# Tachometer-Board.net
KiCad netlist of a schematic drawn in Altium Designer
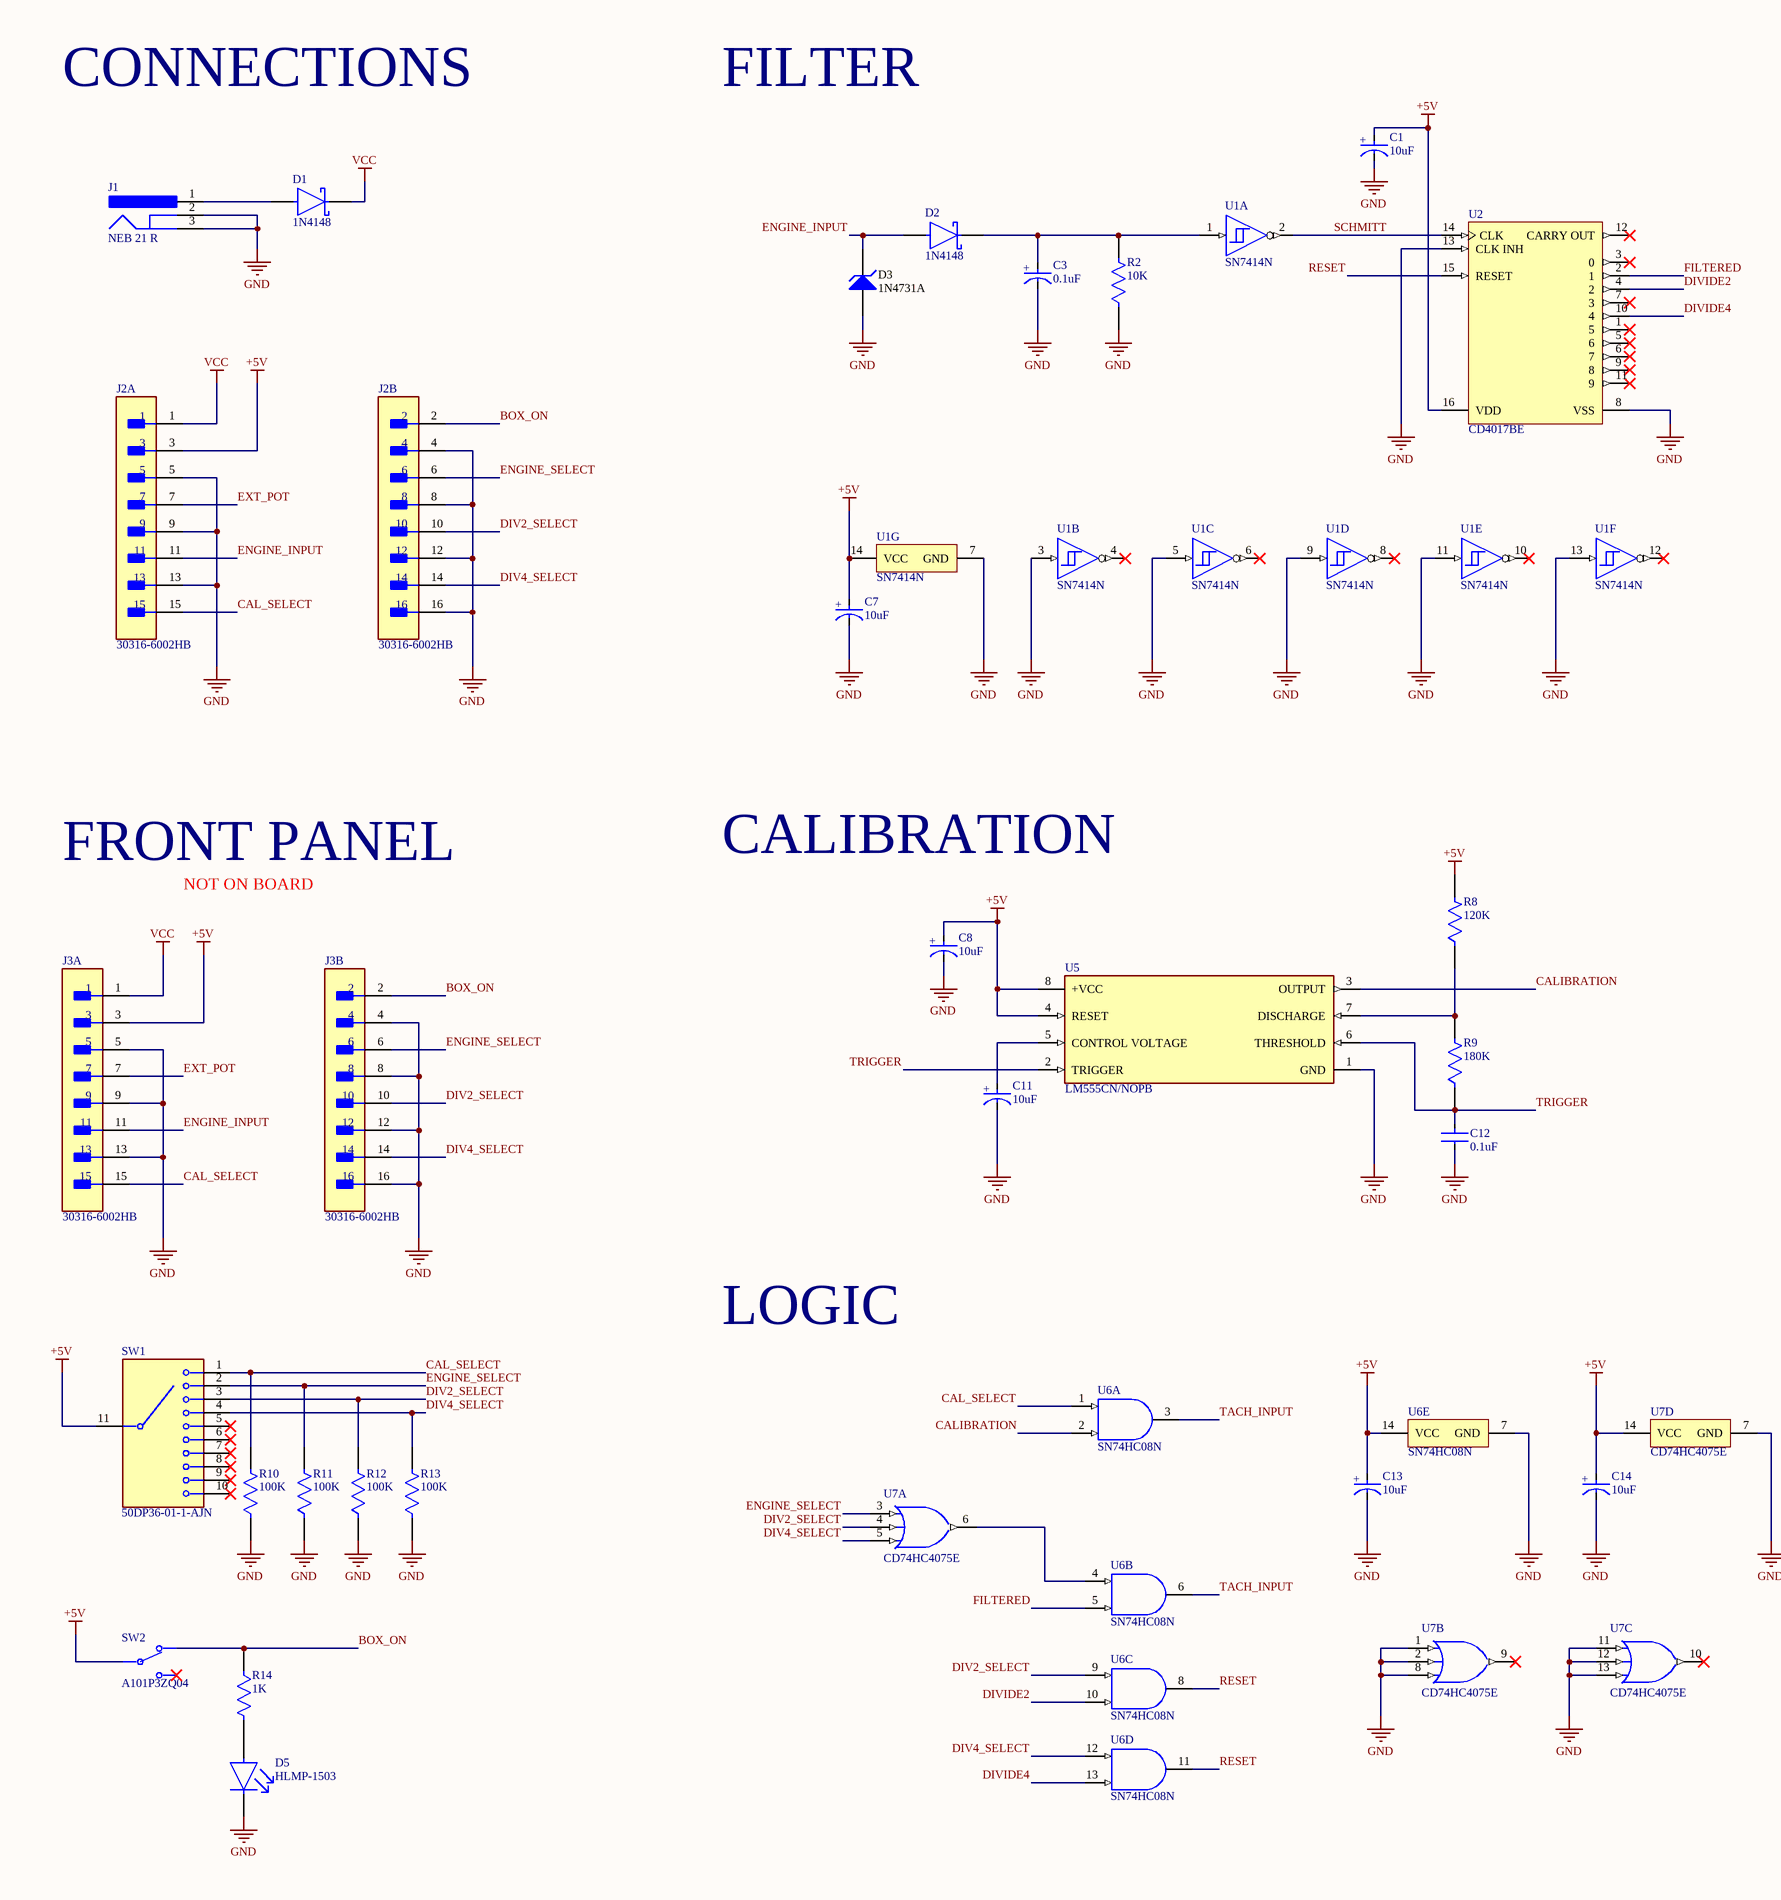
[diagram p0: Tachometer-Board.SchDoc, left]
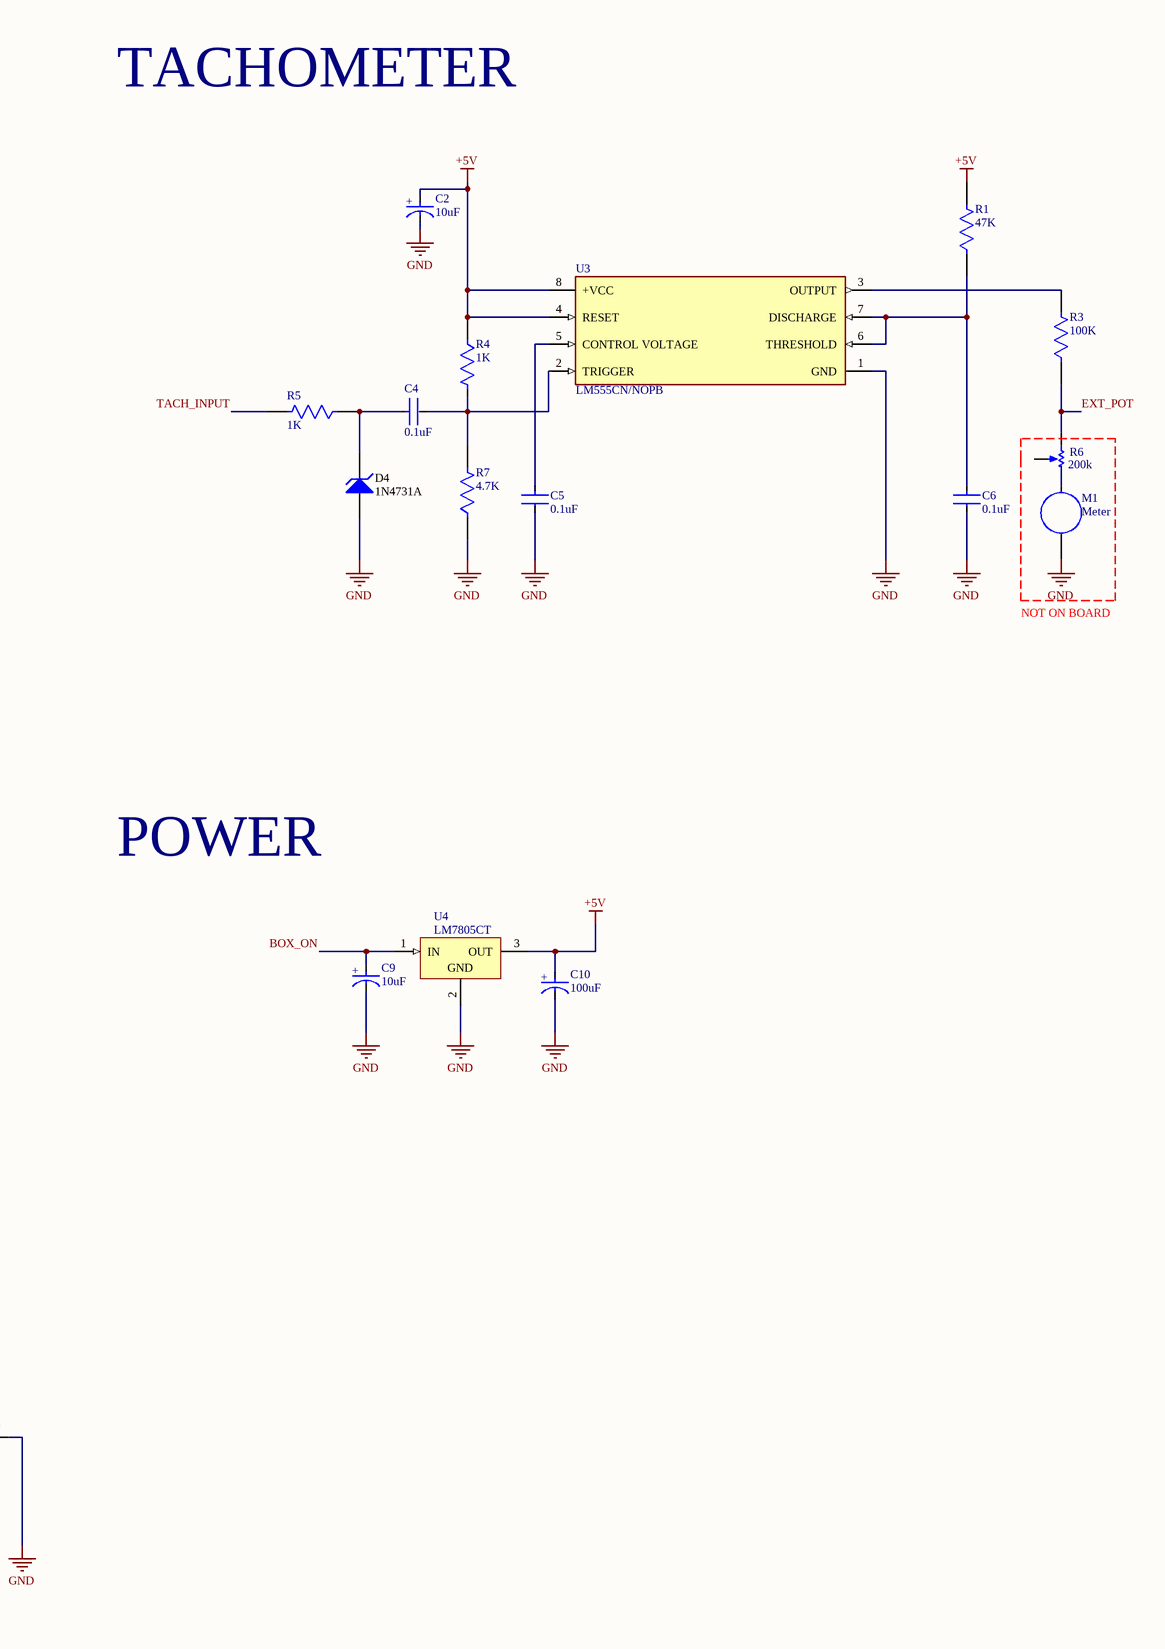
[diagram p1: Tachometer-Board.SchDoc, right]

(export (version "E")
  (design (tool "Eeschema 10.0.6"))
  (components
    (comp (ref "C1")
      (value "10uF")
      (footprint "FP-ESLE3-MFG")
      (description "CAP ALUM 10UF 20% 100V THRU HOLE")
      (fields (field (name "TOLERANCE") "20%") (field (name "MANUFACTURER PART NUMBER") "ESL106M100AE3AA"))
      (libsource (lib "Altium Content Vault") (part "cf48714ba7e38822c1575c7ec0b6d1f"))
    )
    (comp (ref "C2")
      (value "10uF")
      (footprint "FP-ESLE3-MFG")
      (description "CAP ALUM 10UF 20% 100V THRU HOLE")
      (fields (field (name "TOLERANCE") "20%") (field (name "MANUFACTURER PART NUMBER") "ESL106M100AE3AA"))
      (libsource (lib "Altium Content Vault") (part "cf48714ba7e38822c1575c7ec0b6d1f"))
    )
    (comp (ref "C3")
      (value "0.1uF")
      (footprint "FP-ESLE3-MFG")
      (description "CAP ALUM 10UF 20% 100V THRU HOLE")
      (fields (field (name "TOLERANCE") "20%") (field (name "MANUFACTURER PART NUMBER") "ESL106M100AE3AA"))
      (libsource (lib "Altium Content Vault") (part "cf48714ba7e38822c1575c7ec0b6d1f"))
    )
    (comp (ref "C4")
      (value "0.1uF")
      (footprint "FP-K15H5-MFG")
      (description "CAP CER 0.1UF 50V X7R RADIAL")
      (fields (field (name "VOLTAGE") "50V") (field (name "TOLERANCE") "10%"))
      (libsource (lib "Altium Content Vault") (part "11868f565c42a9108669ba33697ecf6"))
    )
    (comp (ref "C5")
      (value "0.1uF")
      (footprint "FP-K15H5-MFG")
      (description "CAP CER 0.1UF 50V X7R RADIAL")
      (fields (field (name "VOLTAGE") "50V") (field (name "TOLERANCE") "10%"))
      (libsource (lib "Altium Content Vault") (part "11868f565c42a9108669ba33697ecf6"))
    )
    (comp (ref "C6")
      (value "0.1uF")
      (footprint "FP-K15H5-MFG")
      (description "CAP CER 0.1UF 50V X7R RADIAL")
      (fields (field (name "VOLTAGE") "50V") (field (name "TOLERANCE") "10%"))
      (libsource (lib "Altium Content Vault") (part "11868f565c42a9108669ba33697ecf6"))
    )
    (comp (ref "C7")
      (value "10uF")
      (footprint "FP-ESLE3-MFG")
      (description "CAP ALUM 10UF 20% 100V THRU HOLE")
      (fields (field (name "TOLERANCE") "20%") (field (name "MANUFACTURER PART NUMBER") "ESL106M100AE3AA"))
      (libsource (lib "Altium Content Vault") (part "cf48714ba7e38822c1575c7ec0b6d1f"))
    )
    (comp (ref "C8")
      (value "10uF")
      (footprint "FP-ESLE3-MFG")
      (description "CAP ALUM 10UF 20% 100V THRU HOLE")
      (fields (field (name "TOLERANCE") "20%") (field (name "MANUFACTURER PART NUMBER") "ESL106M100AE3AA"))
      (libsource (lib "Altium Content Vault") (part "cf48714ba7e38822c1575c7ec0b6d1f"))
    )
    (comp (ref "C9")
      (value "10uF")
      (footprint "FP-ESLE3-MFG")
      (description "CAP ALUM 10UF 20% 100V THRU HOLE")
      (fields (field (name "TOLERANCE") "20%") (field (name "MANUFACTURER PART NUMBER") "ESL106M100AE3AA"))
      (libsource (lib "Altium Content Vault") (part "cf48714ba7e38822c1575c7ec0b6d1f"))
    )
    (comp (ref "C10")
      (value "100uF")
      (footprint "FP-ZLG6_3X7-MFG")
      (description "CAP ALUM 100UF 20% 10V RADIAL")
      (fields
        (field (name "OCTOPART") "https://octopart.com/10zlg100mefc6.3x7-rubycon-19991480")
        (field (name "MANUFACTURER PART NUMBER") "10ZLG100MEFC6.3X7")
      )
      (libsource (lib "Altium Content Vault") (part "cf48714ba7e38822c1575c7ec0b6d1f"))
    )
    (comp (ref "C11")
      (value "10uF")
      (footprint "FP-ESLE3-MFG")
      (description "CAP ALUM 10UF 20% 100V THRU HOLE")
      (fields (field (name "TOLERANCE") "20%") (field (name "MANUFACTURER PART NUMBER") "ESL106M100AE3AA"))
      (libsource (lib "Altium Content Vault") (part "cf48714ba7e38822c1575c7ec0b6d1f"))
    )
    (comp (ref "C12")
      (value "0.1uF")
      (footprint "FP-K15H5-MFG")
      (description "CAP CER 0.1UF 50V X7R RADIAL")
      (fields (field (name "VOLTAGE") "50V") (field (name "TOLERANCE") "10%"))
      (libsource (lib "Altium Content Vault") (part "11868f565c42a9108669ba33697ecf6"))
    )
    (comp (ref "C13")
      (value "10uF")
      (footprint "FP-ESLE3-MFG")
      (description "CAP ALUM 10UF 20% 100V THRU HOLE")
      (fields (field (name "TOLERANCE") "20%") (field (name "MANUFACTURER PART NUMBER") "ESL106M100AE3AA"))
      (libsource (lib "Altium Content Vault") (part "cf48714ba7e38822c1575c7ec0b6d1f"))
    )
    (comp (ref "C14")
      (value "10uF")
      (footprint "FP-ESLE3-MFG")
      (description "CAP ALUM 10UF 20% 100V THRU HOLE")
      (fields (field (name "TOLERANCE") "20%") (field (name "MANUFACTURER PART NUMBER") "ESL106M100AE3AA"))
      (libsource (lib "Altium Content Vault") (part "cf48714ba7e38822c1575c7ec0b6d1f"))
    )
    (comp (ref "D1")
      (value "1N4148")
      (footprint "FP-DO-201AD-MFG")
      (description "DIODE SCHOTTKY 40V 3A DO201AD")
      (fields
        (field (name "MANUFACTURER PART NUMBER") "1N5822")
        (field (name "OCTOPART") "https://octopart.com/1n5822-stmicroelectronics-323225")
      )
      (libsource (lib "Altium Content Vault") (part "1d6ec82d83fb6aee721767c19dac4b9"))
    )
    (comp (ref "D2")
      (value "1N4148")
      (footprint "FP-DO-201AD-MFG")
      (description "DIODE SCHOTTKY 40V 3A DO201AD")
      (fields
        (field (name "MANUFACTURER PART NUMBER") "1N5822")
        (field (name "OCTOPART") "https://octopart.com/1n5822-stmicroelectronics-323225")
      )
      (libsource (lib "Altium Content Vault") (part "1d6ec82d83fb6aee721767c19dac4b9"))
    )
    (comp (ref "D3")
      (value "1N4731A")
      (footprint "FAIR-DO-41-2_V")
      (description "Zener Diode, 4.3V, 1W, 5%, -65 to 200 degC, 2-Pin DO-41, Body 2.72 x 5.2 mm, RoHS")
      (fields (field (name "MANUFACTURER") "Fairchild Semiconductor") (field (name "TOLERANCE") "5%"))
      (libsource (lib "Altium Content Vault") (part "FAIR-DZEN-A1K2-2"))
    )
    (comp (ref "D4")
      (value "1N4731A")
      (footprint "FAIR-DO-41-2_V")
      (description "Zener Diode, 4.3V, 1W, 5%, -65 to 200 degC, 2-Pin DO-41, Body 2.72 x 5.2 mm, RoHS")
      (fields (field (name "MANUFACTURER") "Fairchild Semiconductor") (field (name "TOLERANCE") "5%"))
      (libsource (lib "Altium Content Vault") (part "FAIR-DZEN-A1K2-2"))
    )
    (comp (ref "D5")
      (value "HLMP-1503")
      (footprint "FP-HLMP-1503-MFG")
      (description "LED GREEN DIFFUSED T-1 T/H")
      (fields
        (field (name "MANUFACTURER") "Broadcom")
        (field (name "OCTOPART") "https://octopart.com/hlmp-1503-broadcom-71130371")
      )
      (libsource (lib "Altium Content Vault") (part "8706943c75ba83719d021d2fdc84c58"))
    )
    (comp (ref "J1")
      (value "NEB 21 R")
      (footprint "LUMB-NEB21R_V")
      (description "Jack Socket, Body 14.5 x 9 mm, Height 11 mm, -20 to 70 degC, 3-Pin THD, RoHS, Bulk")
      (fields (field (name "MANUFACTURER") "Lumberg"))
      (libsource (lib "Altium Content Vault") (part "JACK-2CD3-RN"))
    )
    (comp (ref "J2")
      (value "30316-6002HB")
      (footprint "FP-30316-6002HB-MFG")
      (description "CONN HEADER VERT 16POS 2.54MM")
      (fields
        (field (name "OCTOPART") "https://octopart.com/30316-6002hb-3m-653367")
        (field (name "MANUFACTURER") "3M")
      )
      (libsource (lib "Altium Content Vault") (part "4b6d22b45e2f925f038cba5d936fbcc"))
    )
    (comp (ref "J3")
      (value "30316-6002HB")
      (footprint "FP-30316-6002HB-MFG")
      (description "CONN HEADER VERT 16POS 2.54MM")
      (fields
        (field (name "OCTOPART") "https://octopart.com/30316-6002hb-3m-653367")
        (field (name "MANUFACTURER") "3M")
      )
      (libsource (lib "Altium Content Vault") (part "4b6d22b45e2f925f038cba5d936fbcc"))
    )
    (comp (ref "M1")
      (value "Meter")
      (footprint "RAD-0.1")
      (description "Indicating Instrument")
      (fields (field (name "PUBLISHER") "Altium Limited"))
      (libsource (lib "Miscellaneous Devices") (part "Meter"))
    )
    (comp (ref "R1")
      (value "47K")
      (footprint "FP-MFR-25-MFG")
      (description "RES 1.18K OHM 1/4W 1% AXIAL")
      (fields (field (name "MANUFACTURER") "Yageo") (field (name "TOLERANCE") "1%"))
      (libsource (lib "Altium Content Vault") (part "1029c3af85768c4190bb7ad29bc67b5"))
    )
    (comp (ref "R2")
      (value "10K")
      (footprint "FP-MFR-25-MFG")
      (description "RES 1.18K OHM 1/4W 1% AXIAL")
      (fields (field (name "MANUFACTURER") "Yageo") (field (name "TOLERANCE") "1%"))
      (libsource (lib "Altium Content Vault") (part "1029c3af85768c4190bb7ad29bc67b5"))
    )
    (comp (ref "R3")
      (value "100K")
      (footprint "FP-MFR-25-MFG")
      (description "RES 1.18K OHM 1/4W 1% AXIAL")
      (fields (field (name "MANUFACTURER") "Yageo") (field (name "TOLERANCE") "1%"))
      (libsource (lib "Altium Content Vault") (part "1029c3af85768c4190bb7ad29bc67b5"))
    )
    (comp (ref "R4")
      (value "1K")
      (footprint "FP-MFR-25-MFG")
      (description "RES 1.18K OHM 1/4W 1% AXIAL")
      (fields (field (name "MANUFACTURER") "Yageo") (field (name "TOLERANCE") "1%"))
      (libsource (lib "Altium Content Vault") (part "1029c3af85768c4190bb7ad29bc67b5"))
    )
    (comp (ref "R5")
      (value "1K")
      (footprint "FP-MFR-25-MFG")
      (description "RES 1.18K OHM 1/4W 1% AXIAL")
      (fields (field (name "MANUFACTURER") "Yageo") (field (name "TOLERANCE") "1%"))
      (libsource (lib "Altium Content Vault") (part "1029c3af85768c4190bb7ad29bc67b5"))
    )
    (comp (ref "R6")
      (value "200k")
      (footprint "VR5")
      (description "Potentiometer")
      (fields (field (name "Comment") "RPot") (field (name "PUBLISHER") "Altium Limited"))
      (libsource (lib "Miscellaneous Devices") (part "RPot"))
    )
    (comp (ref "R7")
      (value "4.7K")
      (footprint "FP-MFR-25-MFG")
      (description "RES 1.18K OHM 1/4W 1% AXIAL")
      (fields (field (name "MANUFACTURER") "Yageo") (field (name "TOLERANCE") "1%"))
      (libsource (lib "Altium Content Vault") (part "1029c3af85768c4190bb7ad29bc67b5"))
    )
    (comp (ref "R8")
      (value "120K")
      (footprint "FP-MFR-25-MFG")
      (description "RES 1.18K OHM 1/4W 1% AXIAL")
      (fields (field (name "MANUFACTURER") "Yageo") (field (name "TOLERANCE") "1%"))
      (libsource (lib "Altium Content Vault") (part "1029c3af85768c4190bb7ad29bc67b5"))
    )
    (comp (ref "R9")
      (value "180K")
      (footprint "FP-MFR-25-MFG")
      (description "RES 1.18K OHM 1/4W 1% AXIAL")
      (fields (field (name "MANUFACTURER") "Yageo") (field (name "TOLERANCE") "1%"))
      (libsource (lib "Altium Content Vault") (part "1029c3af85768c4190bb7ad29bc67b5"))
    )
    (comp (ref "R10")
      (value "100K")
      (footprint "FP-MFR-25-MFG")
      (description "RES 1.18K OHM 1/4W 1% AXIAL")
      (fields (field (name "MANUFACTURER") "Yageo") (field (name "TOLERANCE") "1%"))
      (libsource (lib "Altium Content Vault") (part "1029c3af85768c4190bb7ad29bc67b5"))
    )
    (comp (ref "R11")
      (value "100K")
      (footprint "FP-MFR-25-MFG")
      (description "RES 1.18K OHM 1/4W 1% AXIAL")
      (fields (field (name "MANUFACTURER") "Yageo") (field (name "TOLERANCE") "1%"))
      (libsource (lib "Altium Content Vault") (part "1029c3af85768c4190bb7ad29bc67b5"))
    )
    (comp (ref "R12")
      (value "100K")
      (footprint "FP-MFR-25-MFG")
      (description "RES 1.18K OHM 1/4W 1% AXIAL")
      (fields (field (name "MANUFACTURER") "Yageo") (field (name "TOLERANCE") "1%"))
      (libsource (lib "Altium Content Vault") (part "1029c3af85768c4190bb7ad29bc67b5"))
    )
    (comp (ref "R13")
      (value "100K")
      (footprint "FP-MFR-25-MFG")
      (description "RES 1.18K OHM 1/4W 1% AXIAL")
      (fields (field (name "MANUFACTURER") "Yageo") (field (name "TOLERANCE") "1%"))
      (libsource (lib "Altium Content Vault") (part "1029c3af85768c4190bb7ad29bc67b5"))
    )
    (comp (ref "R14")
      (value "1K")
      (footprint "FP-MFR-25-MFG")
      (description "RES 1.18K OHM 1/4W 1% AXIAL")
      (fields (field (name "MANUFACTURER") "Yageo") (field (name "TOLERANCE") "1%"))
      (libsource (lib "Altium Content Vault") (part "1029c3af85768c4190bb7ad29bc67b5"))
    )
    (comp (ref "SW1")
      (value "50DP36-01-1-AJN")
      (footprint "FP-50DP36-01-1-AJN-MFG")
      (description "SWITCH ROTARY 2-10POS 150MA 115V")
      (libsource (lib "Altium Content Vault") (part "5c144e7f36cb4f58f9c3166ce3b8b0a"))
    )
    (comp (ref "SW2")
      (value "A101P3ZQ04")
      (footprint "FP-A101P3ZQ04-MFG")
      (description "SWITCH TOGGLE SPDT 5A 120V")
      (libsource (lib "Altium Content Vault") (part "3e9884f9922fbfe170c5e5196286929"))
    )
    (comp (ref "U1")
      (value "SN7414N")
      (footprint "N0014A")
      (description "Hex schmitt-trigger inverters, N0014A, TUBE")
      (fields (field (name "MANUFACTURER") "Texas Instruments") (field (name "GENERIC PART NUMBER") "SN7414"))
      (libsource (lib "Altium Content Vault") (part "TI-CD_SNX4XXXXXX4X_19A-14-SCHMITT"))
    )
    (comp (ref "U2")
      (value "CD4017BE")
      (footprint "N0016A")
      (description "CMOS Decade Counter with 10 Decoded Outputs, N0016A, TUBE")
      (fields
        (field (name "MANUFACTURER") "Texas Instruments")
        (field (name "GENERIC PART NUMBER") "CD4017B")
      )
      (libsource (lib "Altium Content Vault") (part "TI-CD4017B-16"))
    )
    (comp (ref "U3")
      (value "LM555CN/NOPB")
      (footprint "FP-P0008A-MFG")
      (description "IC OSC SINGLE TIMER 100KHZ 8-DIP")
      (fields
        (field (name "MANUFACTURER") "Texas Instruments")
        (field (name "OCTOPART") "https://octopart.com/lm555cn%2Fnopb-texas+instruments-24814897")
      )
      (libsource (lib "Altium Content Vault") (part "8056d98efc272addb90effbbf338635"))
    )
    (comp (ref "U4")
      (value "LM7805CT")
      (footprint "FAIR-TO-220-3")
      (description "Positive Voltage Regulator, 5 V, 1 A, -40 to 125 degC, 3-Pin TO-220, RoHS, Tube")
      (fields (field (name "MANUFACTURER") "FairchildSemiconductor"))
      (libsource (lib "Altium Content Vault") (part "FAIR-LM7805CT-TO220-3"))
    )
    (comp (ref "U5")
      (value "LM555CN/NOPB")
      (footprint "FP-P0008A-MFG")
      (description "IC OSC SINGLE TIMER 100KHZ 8-DIP")
      (fields
        (field (name "MANUFACTURER") "Texas Instruments")
        (field (name "OCTOPART") "https://octopart.com/lm555cn%2Fnopb-texas+instruments-24814897")
      )
      (libsource (lib "Altium Content Vault") (part "8056d98efc272addb90effbbf338635"))
    )
    (comp (ref "U6")
      (value "SN74HC08N")
      (footprint "N0014A")
      (description "Quadruple 2-Input Positive-AND Gates, N0014A, TUBE")
      (fields
        (field (name "GENERIC PART NUMBER") "SN74HC08")
        (field (name "MANUFACTURER") "Texas Instruments")
      )
      (libsource (lib "Altium Content Vault") (part "TI-AND-4-2IN-14"))
    )
    (comp (ref "U7")
      (value "CD74HC4075E")
      (footprint "N0014A")
      (description "High Speed CMOS Logic Triple 3-Input OR Gates, N0014A, TUBE")
      (fields
        (field (name "GENERIC PART NUMBER") "CD74HC4075")
        (field (name "MANUFACTURER") "Texas Instruments")
      )
      (libsource (lib "Altium Content Vault") (part "TI-CD54_74HCX4075-14"))
    )
  )
  (nets
    (net (code "1") (name "+5V") (class "Default")
      (node (ref "C1") (pin "2") (pinfunction "A_2") (pintype "passive"))
      (node (ref "C10") (pin "2") (pinfunction "A_2") (pintype "passive"))
      (node (ref "C13") (pin "2") (pinfunction "A_2") (pintype "passive"))
      (node (ref "C14") (pin "2") (pinfunction "A_2") (pintype "passive"))
      (node (ref "C2") (pin "2") (pinfunction "A_2") (pintype "passive"))
      (node (ref "C7") (pin "2") (pinfunction "A_2") (pintype "passive"))
      (node (ref "C8") (pin "2") (pinfunction "A_2") (pintype "passive"))
      (node (ref "J2") (pin "3") (pinfunction "3_3") (pintype "passive"))
      (node (ref "J3") (pin "3") (pinfunction "3_3") (pintype "passive"))
      (node (ref "R1") (pin "2") (pinfunction "2_2") (pintype "passive"))
      (node (ref "R4") (pin "1") (pinfunction "1_1") (pintype "passive"))
      (node (ref "R8") (pin "2") (pinfunction "2_2") (pintype "passive"))
      (node (ref "SW1") (pin "11") (pinfunction "COMMON_11") (pintype "passive"))
      (node (ref "U1") (pin "14") (pinfunction "VCC_14") (pintype "power_in"))
      (node (ref "U2") (pin "16") (pinfunction "VDD_16") (pintype "power_in"))
      (node (ref "U3") (pin "4") (pinfunction "RESET_4") (pintype "input"))
      (node (ref "U3") (pin "8") (pinfunction "+VCC_8") (pintype "power_in"))
      (node (ref "U4") (pin "3") (pinfunction "OUT_3") (pintype "power_in"))
      (node (ref "U5") (pin "4") (pinfunction "RESET_4") (pintype "input"))
      (node (ref "U5") (pin "8") (pinfunction "+VCC_8") (pintype "power_in"))
      (node (ref "U6") (pin "14") (pinfunction "VCC_14") (pintype "power_in"))
      (node (ref "U7") (pin "14") (pinfunction "VCC_14") (pintype "power_in"))
    )
    (net (code "2") (name "/BOX_ON") (class "Default")
      (node (ref "C9") (pin "2") (pinfunction "A_2") (pintype "passive"))
      (node (ref "J2") (pin "2") (pinfunction "2_2") (pintype "passive"))
      (node (ref "J3") (pin "2") (pinfunction "2_2") (pintype "passive"))
      (node (ref "R14") (pin "1") (pinfunction "1_1") (pintype "passive"))
      (node (ref "U4") (pin "1") (pinfunction "IN_1") (pintype "input"))
    )
    (net (code "3") (name "/CALIBRATION") (class "Default")
      (node (ref "U5") (pin "3") (pinfunction "OUTPUT_3") (pintype "output"))
      (node (ref "U6") (pin "2") (pinfunction "1B_2") (pintype "input"))
    )
    (net (code "4") (name "/CAL_SELECT") (class "Default")
      (node (ref "J2") (pin "15") (pinfunction "15_15") (pintype "passive"))
      (node (ref "J3") (pin "15") (pinfunction "15_15") (pintype "passive"))
      (node (ref "R10") (pin "2") (pinfunction "2_2") (pintype "passive"))
      (node (ref "SW1") (pin "1") (pinfunction "1_1") (pintype "passive"))
      (node (ref "U6") (pin "1") (pinfunction "1A_1") (pintype "input"))
    )
    (net (code "5") (name "/DIV2_SELECT") (class "Default")
      (node (ref "J2") (pin "10") (pinfunction "10_10") (pintype "passive"))
      (node (ref "J3") (pin "10") (pinfunction "10_10") (pintype "passive"))
      (node (ref "R12") (pin "2") (pinfunction "2_2") (pintype "passive"))
      (node (ref "SW1") (pin "3") (pinfunction "3_3") (pintype "passive"))
      (node (ref "U6") (pin "9") (pinfunction "3A_9") (pintype "input"))
      (node (ref "U7") (pin "4") (pinfunction "1B_4") (pintype "input"))
    )
    (net (code "6") (name "/DIV4_SELECT") (class "Default")
      (node (ref "J2") (pin "14") (pinfunction "14_14") (pintype "passive"))
      (node (ref "J3") (pin "14") (pinfunction "14_14") (pintype "passive"))
      (node (ref "R13") (pin "2") (pinfunction "2_2") (pintype "passive"))
      (node (ref "SW1") (pin "4") (pinfunction "4_4") (pintype "passive"))
      (node (ref "U6") (pin "12") (pinfunction "4A_12") (pintype "input"))
      (node (ref "U7") (pin "5") (pinfunction "1C_5") (pintype "input"))
    )
    (net (code "7") (name "/DIVIDE2") (class "Default")
      (node (ref "U2") (pin "4") (pinfunction "2_4") (pintype "output"))
      (node (ref "U6") (pin "10") (pinfunction "3B_10") (pintype "input"))
    )
    (net (code "8") (name "/DIVIDE4") (class "Default")
      (node (ref "U2") (pin "10") (pinfunction "4_10") (pintype "output"))
      (node (ref "U6") (pin "13") (pinfunction "4B_13") (pintype "input"))
    )
    (net (code "9") (name "/ENGINE_INPUT") (class "Default")
      (node (ref "D2") (pin "2") (pinfunction "A_2") (pintype "passive"))
      (node (ref "D3") (pin "2") (pinfunction "K_2") (pintype "passive"))
      (node (ref "J2") (pin "11") (pinfunction "11_11") (pintype "passive"))
      (node (ref "J3") (pin "11") (pinfunction "11_11") (pintype "passive"))
    )
    (net (code "10") (name "/ENGINE_SELECT") (class "Default")
      (node (ref "J2") (pin "6") (pinfunction "6_6") (pintype "passive"))
      (node (ref "J3") (pin "6") (pinfunction "6_6") (pintype "passive"))
      (node (ref "R11") (pin "2") (pinfunction "2_2") (pintype "passive"))
      (node (ref "SW1") (pin "2") (pinfunction "2_2") (pintype "passive"))
      (node (ref "U7") (pin "3") (pinfunction "1A_3") (pintype "input"))
    )
    (net (code "11") (name "/EXT_POT") (class "Default")
      (node (ref "J2") (pin "7") (pinfunction "7_7") (pintype "passive"))
      (node (ref "J3") (pin "7") (pinfunction "7_7") (pintype "passive"))
      (node (ref "R3") (pin "1") (pinfunction "1_1") (pintype "passive"))
      (node (ref "R6") (pin "1") (pinfunction "TOP_1") (pintype "passive"))
    )
    (net (code "12") (name "/FILTERED") (class "Default")
      (node (ref "U2") (pin "2") (pinfunction "1_2") (pintype "output"))
      (node (ref "U6") (pin "5") (pinfunction "2B_5") (pintype "input"))
    )
    (net (code "13") (name "/RESET") (class "Default")
      (node (ref "U2") (pin "15") (pinfunction "RESET_15") (pintype "input"))
      (node (ref "U6") (pin "11") (pinfunction "4Y_11") (pintype "output"))
      (node (ref "U6") (pin "8") (pinfunction "3Y_8") (pintype "passive"))
    )
    (net (code "14") (name "/SCHMITT") (class "Default")
      (node (ref "U1") (pin "2") (pinfunction "~{1Y}_2") (pintype "output"))
      (node (ref "U2") (pin "14") (pinfunction "CLK_14") (pintype "input"))
    )
    (net (code "15") (name "/TACH_INPUT") (class "Default")
      (node (ref "R5") (pin "2") (pinfunction "2_2") (pintype "passive"))
      (node (ref "U6") (pin "3") (pinfunction "1Y_3") (pintype "output"))
      (node (ref "U6") (pin "6") (pinfunction "2Y_6") (pintype "output"))
    )
    (net (code "16") (name "/TRIGGER") (class "Default")
      (node (ref "C12") (pin "1") (pinfunction "1_1") (pintype "passive"))
      (node (ref "R9") (pin "1") (pinfunction "1_1") (pintype "passive"))
      (node (ref "U5") (pin "2") (pinfunction "TRIGGER_2") (pintype "input"))
      (node (ref "U5") (pin "6") (pinfunction "THRESHOLD_6") (pintype "input"))
    )
    (net (code "17") (name "GND") (class "Default")
      (node (ref "C1") (pin "1") (pinfunction "C_1") (pintype "passive"))
      (node (ref "C10") (pin "1") (pinfunction "C_1") (pintype "passive"))
      (node (ref "C11") (pin "1") (pinfunction "C_1") (pintype "passive"))
      (node (ref "C12") (pin "2") (pinfunction "2_2") (pintype "passive"))
      (node (ref "C13") (pin "1") (pinfunction "C_1") (pintype "passive"))
      (node (ref "C14") (pin "1") (pinfunction "C_1") (pintype "passive"))
      (node (ref "C2") (pin "1") (pinfunction "C_1") (pintype "passive"))
      (node (ref "C3") (pin "1") (pinfunction "C_1") (pintype "passive"))
      (node (ref "C5") (pin "2") (pinfunction "2_2") (pintype "passive"))
      (node (ref "C6") (pin "2") (pinfunction "2_2") (pintype "passive"))
      (node (ref "C7") (pin "1") (pinfunction "C_1") (pintype "passive"))
      (node (ref "C8") (pin "1") (pinfunction "C_1") (pintype "passive"))
      (node (ref "C9") (pin "1") (pinfunction "C_1") (pintype "passive"))
      (node (ref "D3") (pin "1") (pinfunction "A_1") (pintype "passive"))
      (node (ref "D4") (pin "1") (pinfunction "A_1") (pintype "passive"))
      (node (ref "D5") (pin "1") (pinfunction "C_1") (pintype "passive"))
      (node (ref "J1") (pin "2") (pinfunction "2_2") (pintype "passive"))
      (node (ref "J1") (pin "3") (pinfunction "3_3") (pintype "passive"))
      (node (ref "J2") (pin "12") (pinfunction "12_12") (pintype "passive"))
      (node (ref "J2") (pin "13") (pinfunction "13_13") (pintype "passive"))
      (node (ref "J2") (pin "16") (pinfunction "16_16") (pintype "passive"))
      (node (ref "J2") (pin "4") (pinfunction "4_4") (pintype "passive"))
      (node (ref "J2") (pin "5") (pinfunction "5_5") (pintype "passive"))
      (node (ref "J2") (pin "8") (pinfunction "8_8") (pintype "passive"))
      (node (ref "J2") (pin "9") (pinfunction "9_9") (pintype "passive"))
      (node (ref "J3") (pin "12") (pinfunction "12_12") (pintype "passive"))
      (node (ref "J3") (pin "13") (pinfunction "13_13") (pintype "passive"))
      (node (ref "J3") (pin "16") (pinfunction "16_16") (pintype "passive"))
      (node (ref "J3") (pin "4") (pinfunction "4_4") (pintype "passive"))
      (node (ref "J3") (pin "5") (pinfunction "5_5") (pintype "passive"))
      (node (ref "J3") (pin "8") (pinfunction "8_8") (pintype "passive"))
      (node (ref "J3") (pin "9") (pinfunction "9_9") (pintype "passive"))
      (node (ref "M1") (pin "1") (pinfunction "1_1") (pintype "passive"))
      (node (ref "R10") (pin "1") (pinfunction "1_1") (pintype "passive"))
      (node (ref "R11") (pin "1") (pinfunction "1_1") (pintype "passive"))
      (node (ref "R12") (pin "1") (pinfunction "1_1") (pintype "passive"))
      (node (ref "R13") (pin "1") (pinfunction "1_1") (pintype "passive"))
      (node (ref "R2") (pin "1") (pinfunction "1_1") (pintype "passive"))
      (node (ref "R7") (pin "1") (pinfunction "1_1") (pintype "passive"))
      (node (ref "U1") (pin "11") (pinfunction "5A_11") (pintype "input"))
      (node (ref "U1") (pin "13") (pinfunction "6A_13") (pintype "input"))
      (node (ref "U1") (pin "3") (pinfunction "2A_3") (pintype "input"))
      (node (ref "U1") (pin "5") (pinfunction "3A_5") (pintype "input"))
      (node (ref "U1") (pin "7") (pinfunction "GND_7") (pintype "power_in"))
      (node (ref "U1") (pin "9") (pinfunction "4A_9") (pintype "input"))
      (node (ref "U2") (pin "13") (pinfunction "CLK_INH_13") (pintype "input"))
      (node (ref "U2") (pin "8") (pinfunction "VSS_8") (pintype "power_in"))
      (node (ref "U3") (pin "1") (pinfunction "GND_1") (pintype "power_in"))
      (node (ref "U4") (pin "2") (pinfunction "GND_2") (pintype "power_in"))
      (node (ref "U5") (pin "1") (pinfunction "GND_1") (pintype "power_in"))
      (node (ref "U6") (pin "7") (pinfunction "GND_7") (pintype "power_in"))
      (node (ref "U7") (pin "1") (pinfunction "2A_1") (pintype "input"))
      (node (ref "U7") (pin "11") (pinfunction "3A_11") (pintype "input"))
      (node (ref "U7") (pin "12") (pinfunction "3B_12") (pintype "input"))
      (node (ref "U7") (pin "13") (pinfunction "3C_13") (pintype "input"))
      (node (ref "U7") (pin "2") (pinfunction "2B_2") (pintype "input"))
      (node (ref "U7") (pin "7") (pinfunction "GND_7") (pintype "power_in"))
      (node (ref "U7") (pin "8") (pinfunction "2C_8") (pintype "input"))
    )
    (net (code "18") (name "Net-(C3-A)") (class "Default")
      (node (ref "C3") (pin "2") (pinfunction "A_2") (pintype "passive"))
      (node (ref "D2") (pin "1") (pinfunction "C_1") (pintype "passive"))
      (node (ref "R2") (pin "2") (pinfunction "2_2") (pintype "passive"))
      (node (ref "U1") (pin "1") (pinfunction "1A_1") (pintype "input"))
    )
    (net (code "19") (name "Net-(C11-A)") (class "Default")
      (node (ref "C11") (pin "2") (pinfunction "A_2") (pintype "passive"))
      (node (ref "U5") (pin "5") (pinfunction "CONTROL_VOLTAGE_5") (pintype "input"))
    )
    (net (code "20") (name "Net-(D1-A)") (class "Default")
      (node (ref "D1") (pin "2") (pinfunction "A_2") (pintype "passive"))
      (node (ref "J1") (pin "1") (pinfunction "1_1") (pintype "passive"))
    )
    (net (code "21") (name "Net-(D4-K)") (class "Default")
      (node (ref "C4") (pin "1") (pinfunction "1_1") (pintype "passive"))
      (node (ref "D4") (pin "2") (pinfunction "K_2") (pintype "passive"))
      (node (ref "R5") (pin "1") (pinfunction "1_1") (pintype "passive"))
    )
    (net (code "22") (name "Net-(R6-BOT)") (class "Default")
      (node (ref "M1") (pin "2") (pinfunction "2_2") (pintype "passive"))
      (node (ref "R6") (pin "2") (pinfunction "BOT_2") (pintype "passive"))
    )
    (net (code "23") (name "Net-(U3-CONTROL_VOLTAGE)") (class "Default")
      (node (ref "C5") (pin "1") (pinfunction "1_1") (pintype "passive"))
      (node (ref "U3") (pin "5") (pinfunction "CONTROL_VOLTAGE_5") (pintype "input"))
    )
    (net (code "24") (name "Net-(U3-DISCHARGE)") (class "Default")
      (node (ref "C6") (pin "1") (pinfunction "1_1") (pintype "passive"))
      (node (ref "R1") (pin "1") (pinfunction "1_1") (pintype "passive"))
      (node (ref "U3") (pin "6") (pinfunction "THRESHOLD_6") (pintype "input"))
      (node (ref "U3") (pin "7") (pinfunction "DISCHARGE_7") (pintype "input"))
    )
    (net (code "25") (name "Net-(U3-OUTPUT)") (class "Default")
      (node (ref "R3") (pin "2") (pinfunction "2_2") (pintype "passive"))
      (node (ref "U3") (pin "3") (pinfunction "OUTPUT_3") (pintype "output"))
    )
    (net (code "26") (name "Net-(U3-TRIGGER)") (class "Default")
      (node (ref "C4") (pin "2") (pinfunction "2_2") (pintype "passive"))
      (node (ref "R4") (pin "2") (pinfunction "2_2") (pintype "passive"))
      (node (ref "R7") (pin "2") (pinfunction "2_2") (pintype "passive"))
      (node (ref "U3") (pin "2") (pinfunction "TRIGGER_2") (pintype "input"))
    )
    (net (code "27") (name "Net-(U5-DISCHARGE)") (class "Default")
      (node (ref "R8") (pin "1") (pinfunction "1_1") (pintype "passive"))
      (node (ref "R9") (pin "2") (pinfunction "2_2") (pintype "passive"))
      (node (ref "U5") (pin "7") (pinfunction "DISCHARGE_7") (pintype "input"))
    )
    (net (code "28") (name "Net-(U6B-2A)") (class "Default")
      (node (ref "U6") (pin "4") (pinfunction "2A_4") (pintype "input"))
      (node (ref "U7") (pin "6") (pinfunction "1Y_6") (pintype "output"))
    )
    (net (code "29") (name "VCC") (class "Default")
      (node (ref "D1") (pin "1") (pinfunction "C_1") (pintype "passive"))
      (node (ref "J2") (pin "1") (pinfunction "1_1") (pintype "passive"))
      (node (ref "J3") (pin "1") (pinfunction "1_1") (pintype "passive"))
    )
    (net (code "30") (name "unconnected-(D5-A-Pad2)") (class "Default")
      (node (ref "D5") (pin "2") (pinfunction "A_2") (pintype "passive"))
    )
    (net (code "31") (name "unconnected-(R6-TAP-Pad3)") (class "Default")
      (node (ref "R6") (pin "3") (pinfunction "TAP_3") (pintype "passive"))
    )
    (net (code "32") (name "unconnected-(R14-Pad2)") (class "Default")
      (node (ref "R14") (pin "2") (pinfunction "2_2") (pintype "passive"))
    )
    (net (code "33") (name "unconnected-(SW1-Pad5)") (class "Default")
      (node (ref "SW1") (pin "5") (pinfunction "5_5") (pintype "passive+no_connect"))
    )
    (net (code "34") (name "unconnected-(SW1-Pad6)") (class "Default")
      (node (ref "SW1") (pin "6") (pinfunction "6_6") (pintype "passive+no_connect"))
    )
    (net (code "35") (name "unconnected-(SW1-Pad7)") (class "Default")
      (node (ref "SW1") (pin "7") (pinfunction "7_7") (pintype "passive+no_connect"))
    )
    (net (code "36") (name "unconnected-(SW1-Pad8)") (class "Default")
      (node (ref "SW1") (pin "8") (pinfunction "8_8") (pintype "passive+no_connect"))
    )
    (net (code "37") (name "unconnected-(SW1-Pad9)") (class "Default")
      (node (ref "SW1") (pin "9") (pinfunction "9_9") (pintype "passive+no_connect"))
    )
    (net (code "38") (name "unconnected-(SW1-Pad10)") (class "Default")
      (node (ref "SW1") (pin "10") (pinfunction "10_10") (pintype "passive+no_connect"))
    )
    (net (code "39") (name "unconnected-(U1B-~{2Y}-Pad4)") (class "Default")
      (node (ref "U1") (pin "4") (pinfunction "~{2Y}_4") (pintype "output+no_connect"))
    )
    (net (code "40") (name "unconnected-(U1C-~{3Y}-Pad6)") (class "Default")
      (node (ref "U1") (pin "6") (pinfunction "~{3Y}_6") (pintype "output+no_connect"))
    )
    (net (code "41") (name "unconnected-(U1D-~{4Y}-Pad8)") (class "Default")
      (node (ref "U1") (pin "8") (pinfunction "~{4Y}_8") (pintype "output+no_connect"))
    )
    (net (code "42") (name "unconnected-(U1E-~{5Y}-Pad10)") (class "Default")
      (node (ref "U1") (pin "10") (pinfunction "~{5Y}_10") (pintype "output+no_connect"))
    )
    (net (code "43") (name "unconnected-(U1F-~{6Y}-Pad12)") (class "Default")
      (node (ref "U1") (pin "12") (pinfunction "~{6Y}_12") (pintype "output+no_connect"))
    )
    (net (code "44") (name "unconnected-(U2-0-Pad3)") (class "Default")
      (node (ref "U2") (pin "3") (pinfunction "0_3") (pintype "output+no_connect"))
    )
    (net (code "45") (name "unconnected-(U2-3-Pad7)") (class "Default")
      (node (ref "U2") (pin "7") (pinfunction "3_7") (pintype "output+no_connect"))
    )
    (net (code "46") (name "unconnected-(U2-5-Pad1)") (class "Default")
      (node (ref "U2") (pin "1") (pinfunction "5_1") (pintype "output+no_connect"))
    )
    (net (code "47") (name "unconnected-(U2-6-Pad5)") (class "Default")
      (node (ref "U2") (pin "5") (pinfunction "6_5") (pintype "output+no_connect"))
    )
    (net (code "48") (name "unconnected-(U2-7-Pad6)") (class "Default")
      (node (ref "U2") (pin "6") (pinfunction "7_6") (pintype "output+no_connect"))
    )
    (net (code "49") (name "unconnected-(U2-8-Pad9)") (class "Default")
      (node (ref "U2") (pin "9") (pinfunction "8_9") (pintype "output+no_connect"))
    )
    (net (code "50") (name "unconnected-(U2-9-Pad11)") (class "Default")
      (node (ref "U2") (pin "11") (pinfunction "9_11") (pintype "output+no_connect"))
    )
    (net (code "51") (name "unconnected-(U2-CARRY_OUT-Pad12)") (class "Default")
      (node (ref "U2") (pin "12") (pinfunction "CARRY_OUT_12") (pintype "output+no_connect"))
    )
    (net (code "52") (name "unconnected-(U7B-2Y-Pad9)") (class "Default")
      (node (ref "U7") (pin "9") (pinfunction "2Y_9") (pintype "output+no_connect"))
    )
    (net (code "53") (name "unconnected-(U7C-3Y-Pad10)") (class "Default")
      (node (ref "U7") (pin "10") (pinfunction "3Y_10") (pintype "output+no_connect"))
    )
  )
)
